# Honey_v2_a.net
KiCad netlist of a schematic drawn in EAGLE
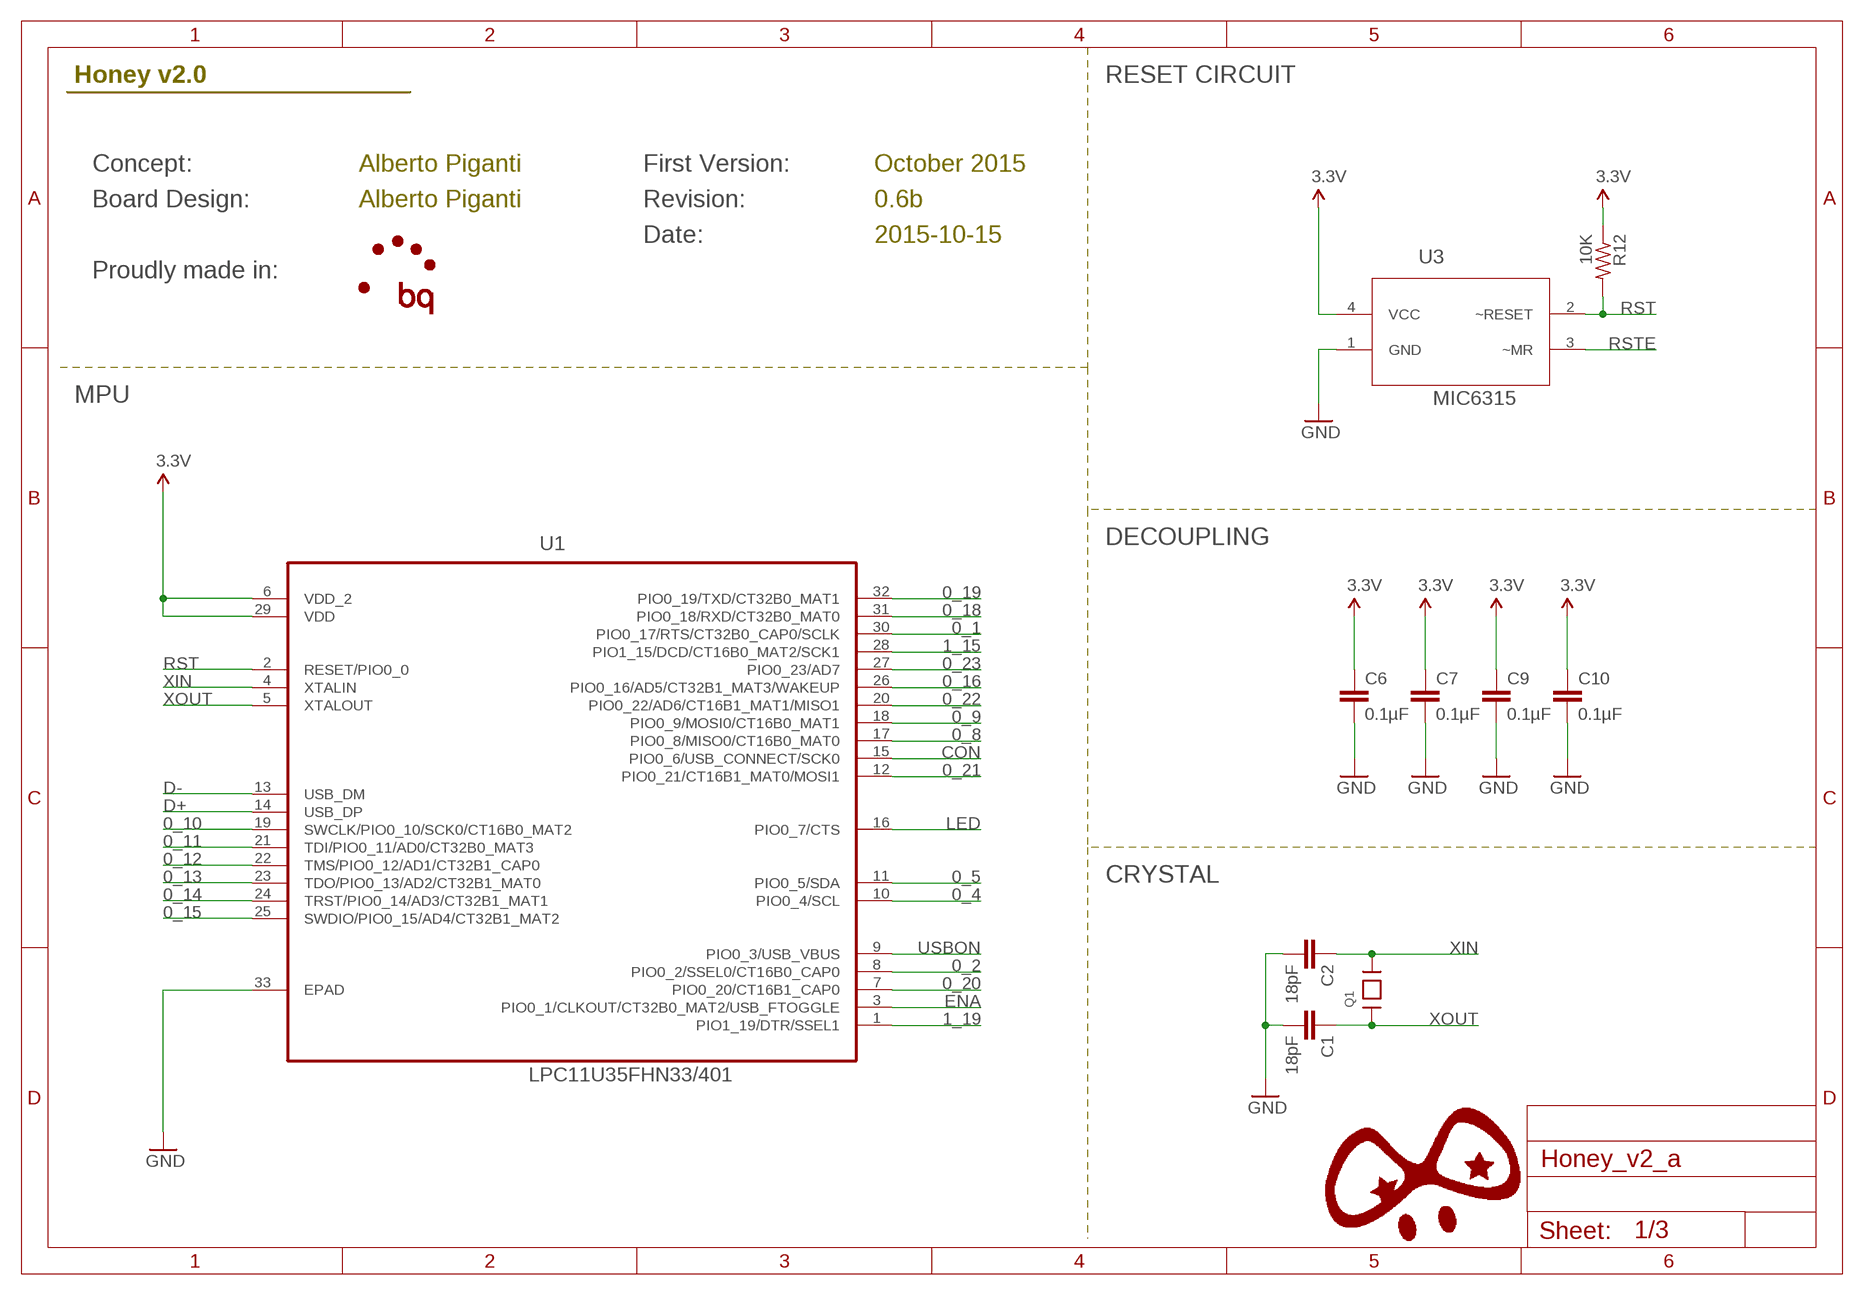
[diagram p0: schematic, sheet 1]
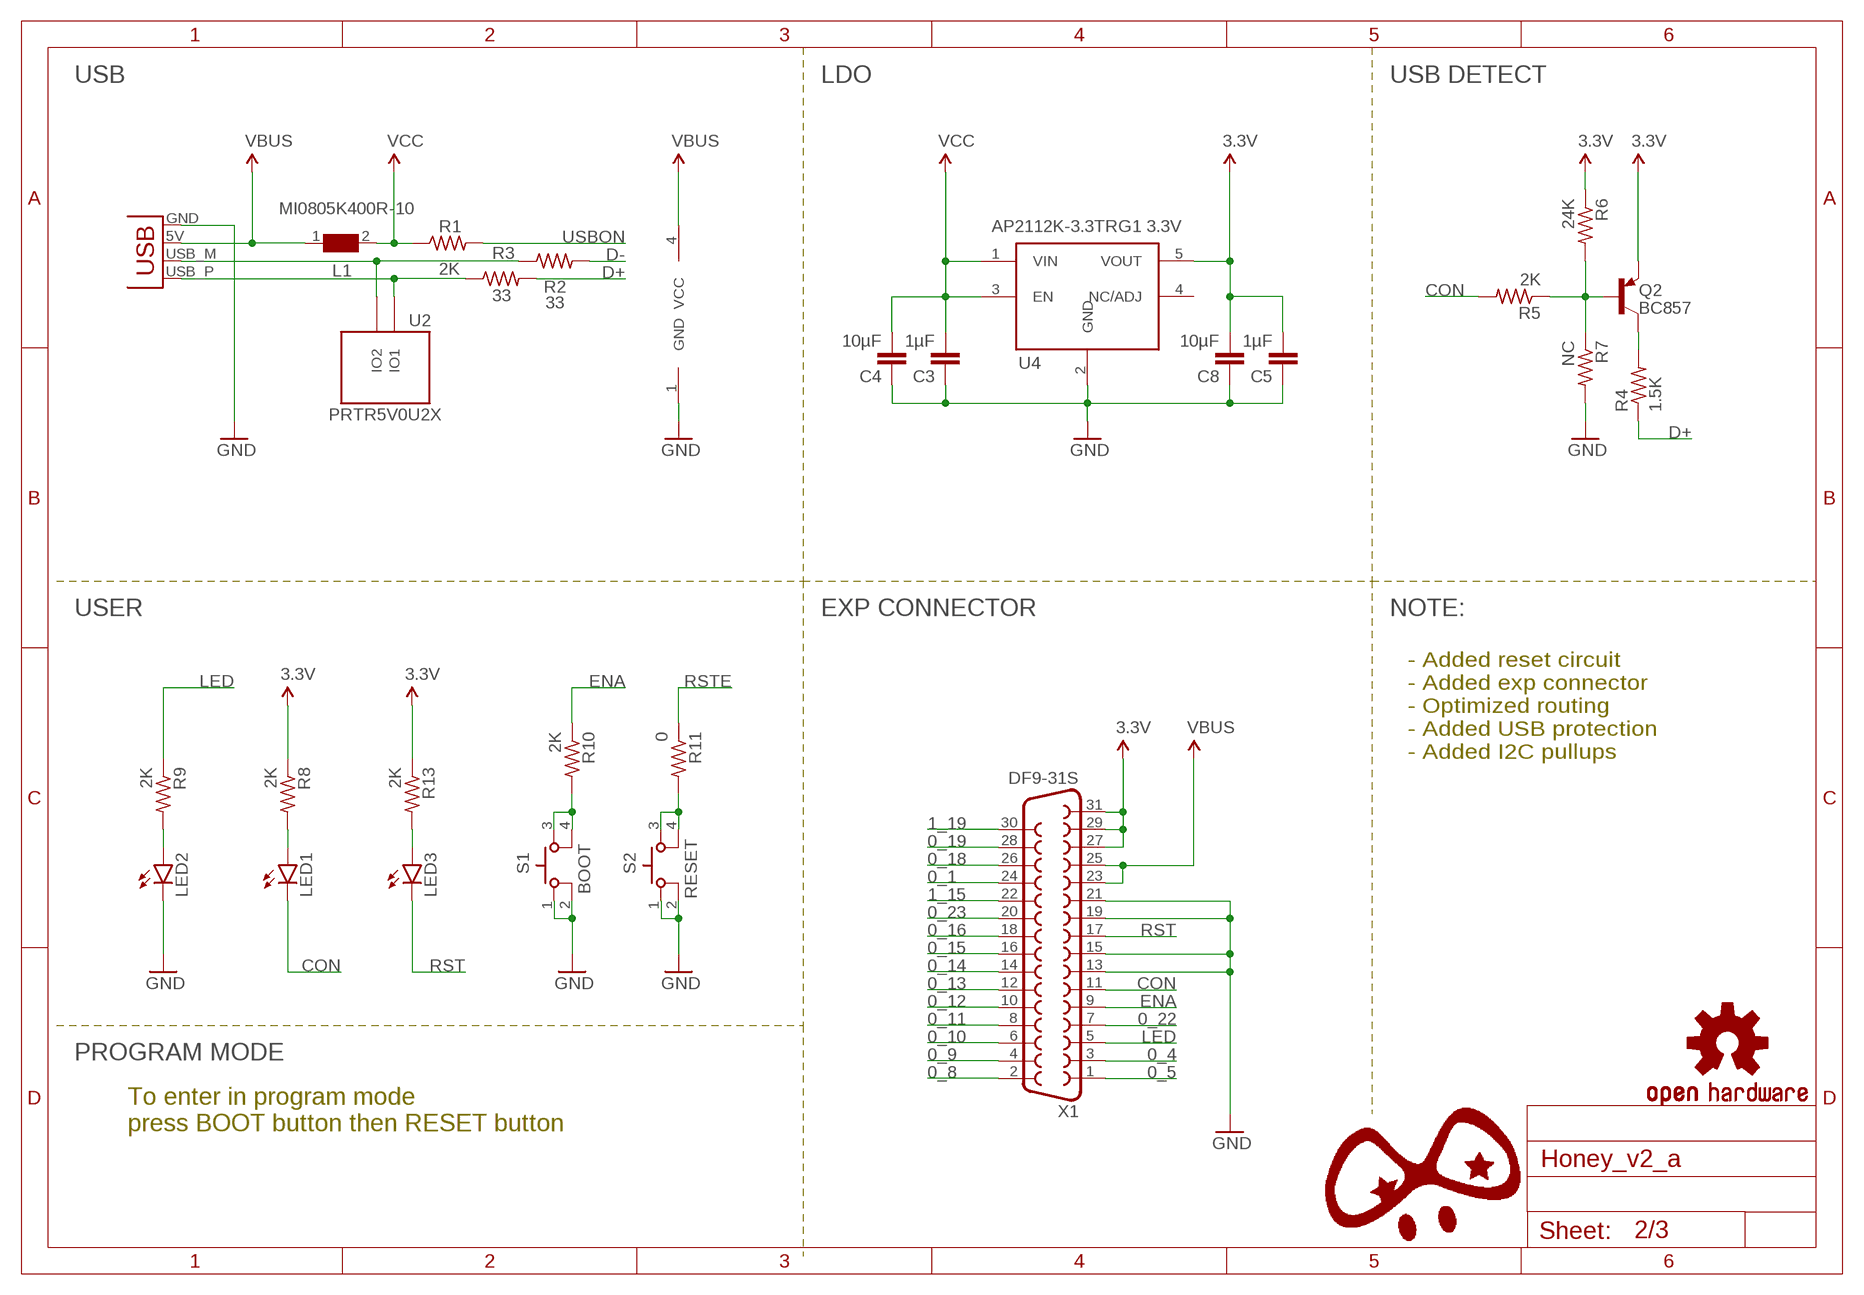
[diagram p1: schematic, sheet 2]
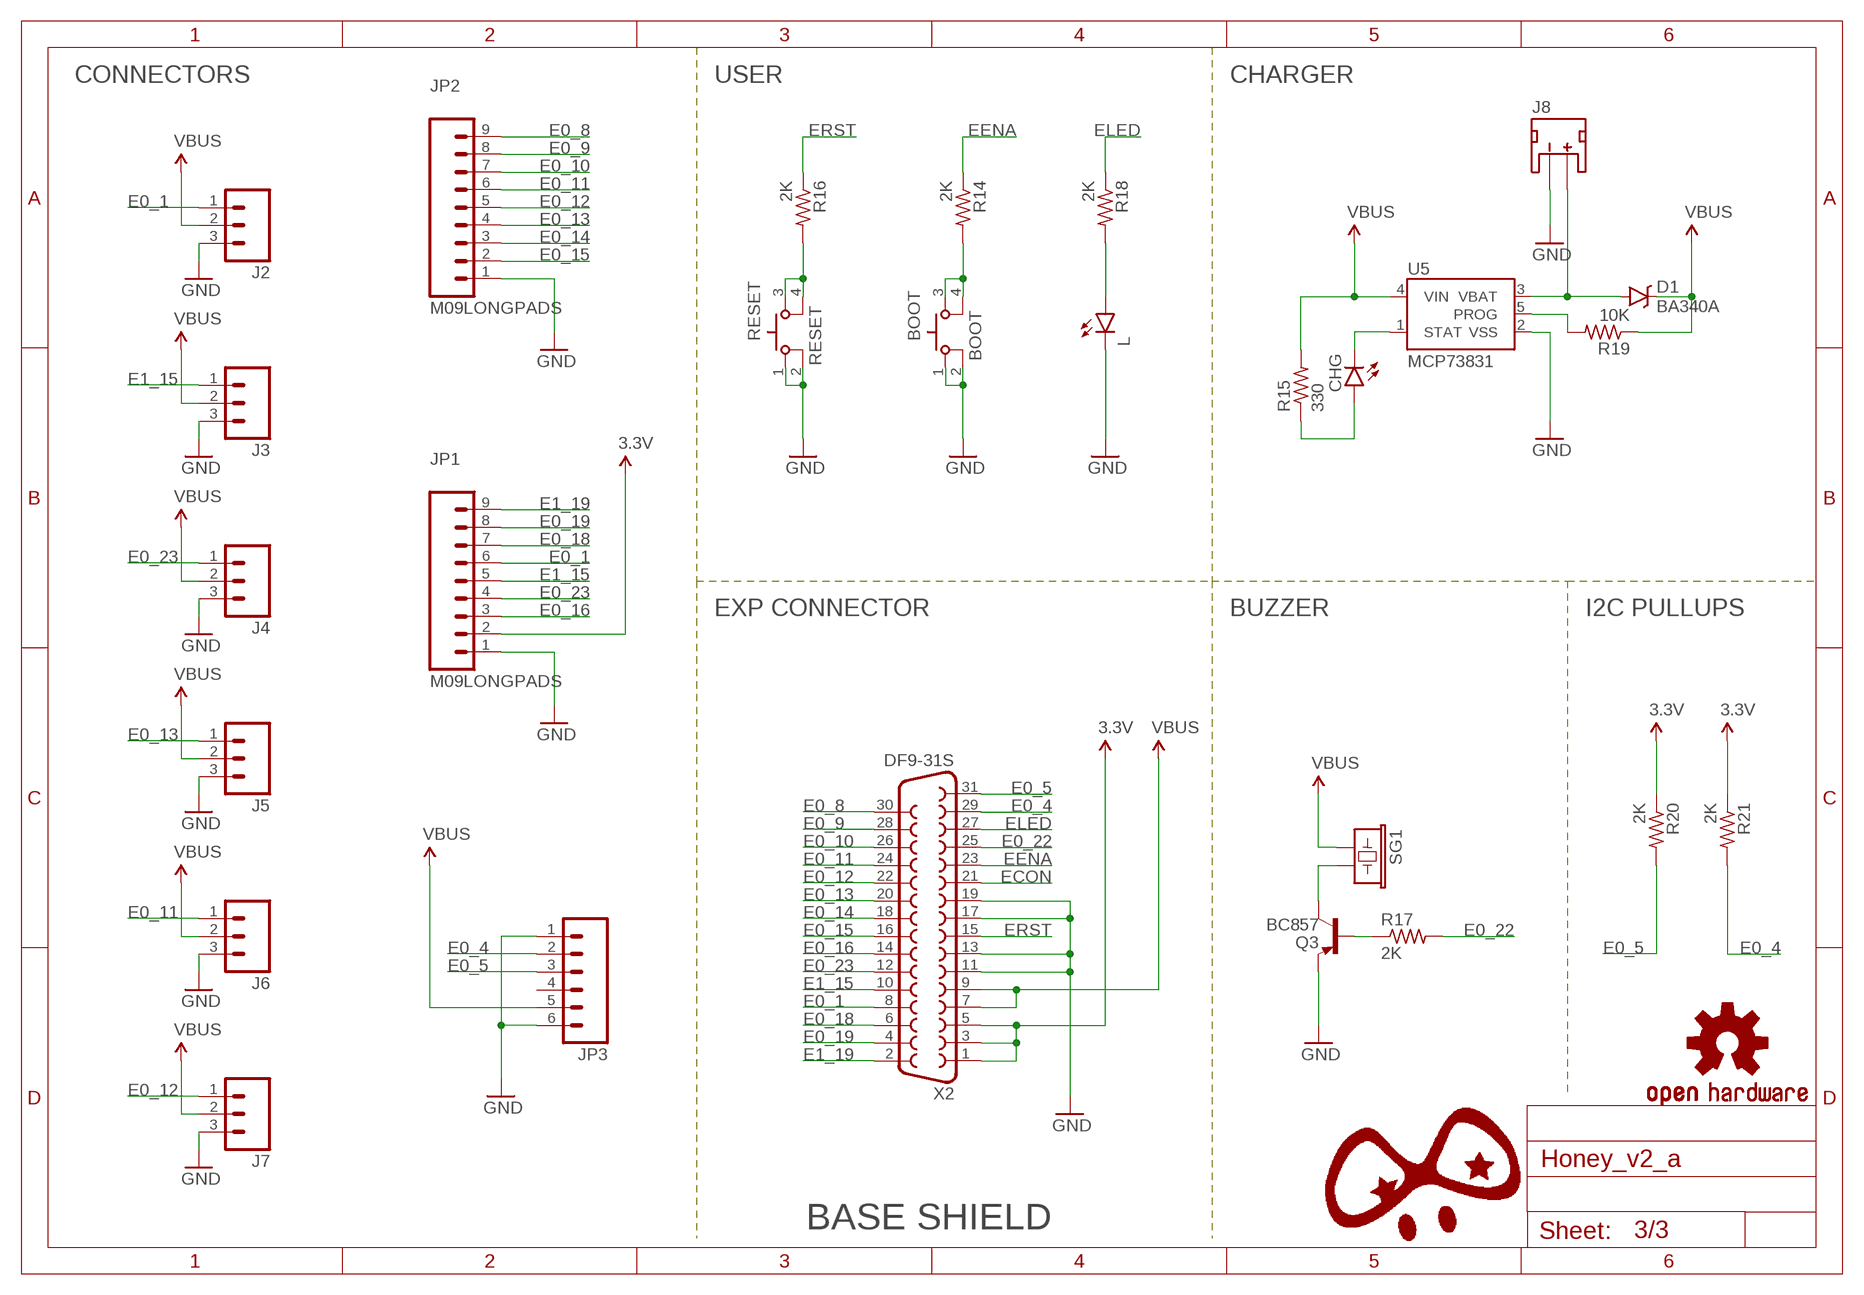
[diagram p2: schematic, sheet 3]

(export (version "E")
  (design (tool "Eeschema 10.0.6"))
  (components
    (comp (ref "C3")
      (value "1µF")
      (footprint "eagle-import:0603-CAP")
      (libsource (lib "eagle-import") (part "CAP0603-CAP"))
    )
    (comp (ref "C4")
      (value "10µF")
      (footprint "eagle-import:0603-CAP")
      (libsource (lib "eagle-import") (part "CAP0603-CAP"))
    )
    (comp (ref "C5")
      (value "1µF")
      (footprint "eagle-import:0603-CAP")
      (libsource (lib "eagle-import") (part "CAP0603-CAP"))
    )
    (comp (ref "C8")
      (value "10µF")
      (footprint "eagle-import:0603-CAP")
      (libsource (lib "eagle-import") (part "CAP0603-CAP"))
    )
    (comp (ref "J1")
      (value "USBPCB")
      (footprint "eagle-import:USB-A-PCB")
      (libsource (lib "eagle-import") (part "USBPCB"))
    )
    (comp (ref "L1")
      (value "MI0805K400R-10")
      (footprint "eagle-import:0805")
      (fields (field (name "MPN") "74279201"))
      (libsource (lib "eagle-import") (part "FERRITE_0805-74279201"))
    )
    (comp (ref "LED1")
      (value "LED0603")
      (footprint "eagle-import:LED-0603")
      (libsource (lib "eagle-import") (part "LED0603"))
    )
    (comp (ref "LED2")
      (value "LED0603")
      (footprint "eagle-import:LED-0603")
      (libsource (lib "eagle-import") (part "LED0603"))
    )
    (comp (ref "LED3")
      (value "LED0603")
      (footprint "eagle-import:LED-0603")
      (libsource (lib "eagle-import") (part "LED0603"))
    )
    (comp (ref "LOGO1")
      (value "OSHW-LOGOS")
      (footprint "eagle-import:OSHW-LOGO-S")
      (libsource (lib "eagle-import") (part "OSHW-LOGOS"))
    )
    (comp (ref "Q2")
      (value "BC857")
      (footprint "eagle-import:SOT23-BEC")
      (libsource (lib "eagle-import") (part "-PNP-SOT23-BECBC857A"))
    )
    (comp (ref "R1")
      (value "2K")
      (footprint "eagle-import:R0402")
      (libsource (lib "eagle-import") (part "R-US_R0402"))
    )
    (comp (ref "R2")
      (value "33")
      (footprint "eagle-import:R0603")
      (libsource (lib "eagle-import") (part "R-US_R0603"))
    )
    (comp (ref "R3")
      (value "33")
      (footprint "eagle-import:R0603")
      (libsource (lib "eagle-import") (part "R-US_R0603"))
    )
    (comp (ref "R4")
      (value "1.5K")
      (footprint "eagle-import:R0402")
      (libsource (lib "eagle-import") (part "R-US_R0402"))
    )
    (comp (ref "R5")
      (value "2K")
      (footprint "eagle-import:R0402")
      (libsource (lib "eagle-import") (part "R-US_R0402"))
    )
    (comp (ref "R6")
      (value "24K")
      (footprint "eagle-import:R0402")
      (libsource (lib "eagle-import") (part "R-US_R0402"))
    )
    (comp (ref "R7")
      (value "NC")
      (footprint "eagle-import:R0402")
      (libsource (lib "eagle-import") (part "R-US_R0402"))
    )
    (comp (ref "R8")
      (value "2K")
      (footprint "eagle-import:R0402")
      (libsource (lib "eagle-import") (part "R-US_R0402"))
    )
    (comp (ref "R9")
      (value "2K")
      (footprint "eagle-import:R0402")
      (libsource (lib "eagle-import") (part "R-US_R0402"))
    )
    (comp (ref "R10")
      (value "2K")
      (footprint "eagle-import:R0402")
      (libsource (lib "eagle-import") (part "R-US_R0402"))
    )
    (comp (ref "R11")
      (value "0")
      (footprint "eagle-import:R0402")
      (libsource (lib "eagle-import") (part "R-US_R0402"))
    )
    (comp (ref "R13")
      (value "2K")
      (footprint "eagle-import:R0402")
      (libsource (lib "eagle-import") (part "R-US_R0402"))
    )
    (comp (ref "S1")
      (value "BOOT")
      (footprint "eagle-import:MINI_PUSHBUTTON")
      (libsource (lib "eagle-import") (part "MINI_PUSHBUTTON"))
    )
    (comp (ref "S2")
      (value "RESET")
      (footprint "eagle-import:MINI_PUSHBUTTON")
      (libsource (lib "eagle-import") (part "MINI_PUSHBUTTON"))
    )
    (comp (ref "U2")
      (value "PRTR5V0U2X")
      (footprint "eagle-import:SOT-143B")
      (fields
        (field (name "MANUFACTURER") "NXP Semiconductors")
        (field (name "PART_NUMBER") "PRTR5V0U2X,215")
      )
      (libsource (lib "eagle-import") (part "PRTR5V0U2X?"))
    )
    (comp (ref "U4")
      (value "AP2112K-3.3TRG1 3.3V")
      (footprint "eagle-import:SOT23-5")
      (libsource (lib "eagle-import") (part "5PIN_REG"))
    )
    (comp (ref "X1")
      (value "DF9-31S")
      (footprint "eagle-import:DF9-31S")
      (fields (field (name "MPN") "DF9-31S-1V(32)"))
      (libsource (lib "eagle-import") (part "DF9-31S"))
    )
    (comp (ref "BOOT")
      (value "BOOT")
      (footprint "eagle-import:MINI_PUSHBUTTON")
      (libsource (lib "eagle-import") (part "MINI_PUSHBUTTON"))
    )
    (comp (ref "CHG")
      (value "LED0603")
      (footprint "eagle-import:LED-0603")
      (libsource (lib "eagle-import") (part "LED0603"))
    )
    (comp (ref "D1")
      (value "BA340A")
      (footprint "eagle-import:SMA-DIODE")
      (libsource (lib "eagle-import") (part "B340A"))
    )
    (comp (ref "J2")
      (value "M03LOCK_NO_SILK")
      (footprint "eagle-import:1X03_LOCK_NO_SILK")
      (libsource (lib "eagle-import") (part "M03LOCK_NO_SILK"))
    )
    (comp (ref "J3")
      (value "M03LOCK_NO_SILK")
      (footprint "eagle-import:1X03_LOCK_NO_SILK")
      (libsource (lib "eagle-import") (part "M03LOCK_NO_SILK"))
    )
    (comp (ref "J4")
      (value "M03LOCK_NO_SILK")
      (footprint "eagle-import:1X03_LOCK_NO_SILK")
      (libsource (lib "eagle-import") (part "M03LOCK_NO_SILK"))
    )
    (comp (ref "J5")
      (value "M03LOCK_NO_SILK")
      (footprint "eagle-import:1X03_LOCK_NO_SILK")
      (libsource (lib "eagle-import") (part "M03LOCK_NO_SILK"))
    )
    (comp (ref "J6")
      (value "M03LOCK_NO_SILK")
      (footprint "eagle-import:1X03_LOCK_NO_SILK")
      (libsource (lib "eagle-import") (part "M03LOCK_NO_SILK"))
    )
    (comp (ref "J7")
      (value "M03LOCK_NO_SILK")
      (footprint "eagle-import:1X03_LOCK_NO_SILK")
      (libsource (lib "eagle-import") (part "M03LOCK_NO_SILK"))
    )
    (comp (ref "J8")
      (value "JST_2MM_MALE")
      (footprint "eagle-import:JST-2-SMD")
      (libsource (lib "eagle-import") (part "JST_2MM_MALE"))
    )
    (comp (ref "JP1")
      (value "M09LONGPADS")
      (footprint "eagle-import:1X09_LONGPADS")
      (libsource (lib "eagle-import") (part "M09LONGPADS"))
    )
    (comp (ref "JP2")
      (value "M09LONGPADS")
      (footprint "eagle-import:1X09_LONGPADS")
      (libsource (lib "eagle-import") (part "M09LONGPADS"))
    )
    (comp (ref "JP3")
      (value "M06LONGPADS")
      (footprint "eagle-import:1X06_LONGPADS")
      (libsource (lib "eagle-import") (part "M06LONGPADS"))
    )
    (comp (ref "L")
      (value "LED0603")
      (footprint "eagle-import:LED-0603")
      (libsource (lib "eagle-import") (part "LED0603"))
    )
    (comp (ref "LOGO4")
      (value "OSHW-LOGOS")
      (footprint "eagle-import:OSHW-LOGO-S")
      (libsource (lib "eagle-import") (part "OSHW-LOGOS"))
    )
    (comp (ref "Q3")
      (value "BC857")
      (footprint "eagle-import:SOT23-BEC")
      (libsource (lib "eagle-import") (part "-PNP-SOT23-BECBC857A"))
    )
    (comp (ref "R14")
      (value "2K")
      (footprint "eagle-import:R0402")
      (libsource (lib "eagle-import") (part "R-US_R0402"))
    )
    (comp (ref "R15")
      (value "330")
      (footprint "eagle-import:R0402")
      (libsource (lib "eagle-import") (part "R-US_R0402"))
    )
    (comp (ref "R16")
      (value "2K")
      (footprint "eagle-import:R0402")
      (libsource (lib "eagle-import") (part "R-US_R0402"))
    )
    (comp (ref "R17")
      (value "2K")
      (footprint "eagle-import:R0402")
      (libsource (lib "eagle-import") (part "R-US_R0402"))
    )
    (comp (ref "R18")
      (value "2K")
      (footprint "eagle-import:R0402")
      (libsource (lib "eagle-import") (part "R-US_R0402"))
    )
    (comp (ref "R19")
      (value "10K")
      (footprint "eagle-import:R0402")
      (libsource (lib "eagle-import") (part "R-US_R0402"))
    )
    (comp (ref "R20")
      (value "2K")
      (footprint "eagle-import:R0402")
      (libsource (lib "eagle-import") (part "R-US_R0402"))
    )
    (comp (ref "R21")
      (value "2K")
      (footprint "eagle-import:R0402")
      (libsource (lib "eagle-import") (part "R-US_R0402"))
    )
    (comp (ref "RESET")
      (value "RESET")
      (footprint "eagle-import:MINI_PUSHBUTTON")
      (libsource (lib "eagle-import") (part "MINI_PUSHBUTTON"))
    )
    (comp (ref "SG1")
      (value "BUZZERSMD2")
      (footprint "eagle-import:BUZZER-CCV")
      (libsource (lib "eagle-import") (part "BUZZERSMD2"))
    )
    (comp (ref "U5")
      (value "MCP73831")
      (footprint "eagle-import:SOT23-5")
      (libsource (lib "eagle-import") (part "MCP73831"))
    )
    (comp (ref "X2")
      (value "DF9-31S")
      (footprint "eagle-import:DF9-31S")
      (fields (field (name "MPN") "DF9-31S-1V(32)"))
      (libsource (lib "eagle-import") (part "DF9-31S"))
    )
    (comp (ref "C1")
      (value "18pF")
      (footprint "eagle-import:C0402")
      (libsource (lib "eagle-import") (part "C-EUC0402"))
    )
    (comp (ref "C2")
      (value "18pF")
      (footprint "eagle-import:C0402")
      (libsource (lib "eagle-import") (part "C-EUC0402"))
    )
    (comp (ref "C6")
      (value "0.1µF")
      (footprint "eagle-import:C0402")
      (libsource (lib "eagle-import") (part "C-EUC0402"))
    )
    (comp (ref "C7")
      (value "0.1µF")
      (footprint "eagle-import:C0402")
      (libsource (lib "eagle-import") (part "C-EUC0402"))
    )
    (comp (ref "C9")
      (value "0.1µF")
      (footprint "eagle-import:C0402")
      (libsource (lib "eagle-import") (part "C-EUC0402"))
    )
    (comp (ref "C10")
      (value "0.1µF")
      (footprint "eagle-import:C0402")
      (libsource (lib "eagle-import") (part "C-EUC0402"))
    )
    (comp (ref "Q1")
      (value "12MHz 4 pad crystal 3.2x2.5")
      (footprint "eagle-import:CRYSTAL_3.2X2.5")
      (libsource (lib "eagle-import") (part "CRYSTAL3.2X2.5"))
    )
    (comp (ref "R12")
      (value "10K")
      (footprint "eagle-import:R0402")
      (libsource (lib "eagle-import") (part "R-US_R0402"))
    )
    (comp (ref "U1")
      (value "LPC11U35FHN33/401")
      (footprint "eagle-import:QFN65P700X700X100-33N")
      (libsource (lib "eagle-import") (part "LPC11U35FHN33/401"))
    )
    (comp (ref "U3")
      (value "MIC6315")
      (footprint "eagle-import:SOT-143B")
      (libsource (lib "eagle-import") (part "MIC6315"))
    )
  )
  (nets
    (net (code "1") (name "0_1") (class "Default")
      (node (ref "U1") (pin "30") (pinfunction "PIO0_17/RTS/CT32B0_CAP0/SCLK_30") (pintype "bidirectional"))
      (node (ref "X1") (pin "24") (pinfunction "24_24") (pintype "passive"))
    )
    (net (code "2") (name "0_2") (class "Default")
      (node (ref "U1") (pin "8") (pinfunction "PIO0_2/SSEL0/CT16B0_CAP0_8") (pintype "bidirectional"))
    )
    (net (code "3") (name "0_4") (class "Default")
      (node (ref "U1") (pin "10") (pinfunction "PIO0_4/SCL_10") (pintype "bidirectional"))
      (node (ref "X1") (pin "3") (pinfunction "3_3") (pintype "passive"))
    )
    (net (code "4") (name "0_5") (class "Default")
      (node (ref "U1") (pin "11") (pinfunction "PIO0_5/SDA_11") (pintype "bidirectional"))
      (node (ref "X1") (pin "1") (pinfunction "1_1") (pintype "passive"))
    )
    (net (code "5") (name "0_8") (class "Default")
      (node (ref "U1") (pin "17") (pinfunction "PIO0_8/MISO0/CT16B0_MAT0_17") (pintype "bidirectional"))
      (node (ref "X1") (pin "2") (pinfunction "2_2") (pintype "passive"))
    )
    (net (code "6") (name "0_9") (class "Default")
      (node (ref "U1") (pin "18") (pinfunction "PIO0_9/MOSI0/CT16B0_MAT1_18") (pintype "bidirectional"))
      (node (ref "X1") (pin "4") (pinfunction "4_4") (pintype "passive"))
    )
    (net (code "7") (name "0_10") (class "Default")
      (node (ref "U1") (pin "19") (pinfunction "SWCLK/PIO0_10/SCK0/CT16B0_MAT2_19") (pintype "input"))
      (node (ref "X1") (pin "6") (pinfunction "6_6") (pintype "passive"))
    )
    (net (code "8") (name "0_11") (class "Default")
      (node (ref "U1") (pin "21") (pinfunction "TDI/PIO0_11/AD0/CT32B0_MAT3_21") (pintype "input"))
      (node (ref "X1") (pin "8") (pinfunction "8_8") (pintype "passive"))
    )
    (net (code "9") (name "0_12") (class "Default")
      (node (ref "U1") (pin "22") (pinfunction "TMS/PIO0_12/AD1/CT32B1_CAP0_22") (pintype "input"))
      (node (ref "X1") (pin "10") (pinfunction "10_10") (pintype "passive"))
    )
    (net (code "10") (name "0_13") (class "Default")
      (node (ref "U1") (pin "23") (pinfunction "TDO/PIO0_13/AD2/CT32B1_MAT0_23") (pintype "output"))
      (node (ref "X1") (pin "12") (pinfunction "12_12") (pintype "passive"))
    )
    (net (code "11") (name "0_14") (class "Default")
      (node (ref "U1") (pin "24") (pinfunction "TRST/PIO0_14/AD3/CT32B1_MAT1_24") (pintype "input"))
      (node (ref "X1") (pin "14") (pinfunction "14_14") (pintype "passive"))
    )
    (net (code "12") (name "0_15") (class "Default")
      (node (ref "U1") (pin "25") (pinfunction "SWDIO/PIO0_15/AD4/CT32B1_MAT2_25") (pintype "output"))
      (node (ref "X1") (pin "16") (pinfunction "16_16") (pintype "passive"))
    )
    (net (code "13") (name "0_16") (class "Default")
      (node (ref "U1") (pin "26") (pinfunction "PIO0_16/AD5/CT32B1_MAT3/WAKEUP_26") (pintype "bidirectional"))
      (node (ref "X1") (pin "18") (pinfunction "18_18") (pintype "passive"))
    )
    (net (code "14") (name "0_18") (class "Default")
      (node (ref "U1") (pin "31") (pinfunction "PIO0_18/RXD/CT32B0_MAT0_31") (pintype "bidirectional"))
      (node (ref "X1") (pin "26") (pinfunction "26_26") (pintype "passive"))
    )
    (net (code "15") (name "0_19") (class "Default")
      (node (ref "U1") (pin "32") (pinfunction "PIO0_19/TXD/CT32B0_MAT1_32") (pintype "bidirectional"))
      (node (ref "X1") (pin "28") (pinfunction "28_28") (pintype "passive"))
    )
    (net (code "16") (name "0_20") (class "Default")
      (node (ref "U1") (pin "7") (pinfunction "PIO0_20/CT16B1_CAP0_7") (pintype "bidirectional"))
    )
    (net (code "17") (name "0_21") (class "Default")
      (node (ref "U1") (pin "12") (pinfunction "PIO0_21/CT16B1_MAT0/MOSI1_12") (pintype "bidirectional"))
    )
    (net (code "18") (name "0_22") (class "Default")
      (node (ref "U1") (pin "20") (pinfunction "PIO0_22/AD6/CT16B1_MAT1/MISO1_20") (pintype "bidirectional"))
      (node (ref "X1") (pin "7") (pinfunction "7_7") (pintype "passive"))
    )
    (net (code "19") (name "0_23") (class "Default")
      (node (ref "U1") (pin "27") (pinfunction "PIO0_23/AD7_27") (pintype "bidirectional"))
      (node (ref "X1") (pin "20") (pinfunction "20_20") (pintype "passive"))
    )
    (net (code "20") (name "1_15") (class "Default")
      (node (ref "U1") (pin "28") (pinfunction "PIO1_15/DCD/CT16B0_MAT2/SCK1_28") (pintype "bidirectional"))
      (node (ref "X1") (pin "22") (pinfunction "22_22") (pintype "passive"))
    )
    (net (code "21") (name "1_19") (class "Default")
      (node (ref "U1") (pin "1") (pinfunction "PIO1_19/DTR/SSEL1_1") (pintype "bidirectional"))
      (node (ref "X1") (pin "30") (pinfunction "30_30") (pintype "passive"))
    )
    (net (code "22") (name "3.3V") (class "Default")
      (node (ref "C10") (pin "1") (pinfunction "1_1") (pintype "passive"))
      (node (ref "C5") (pin "2") (pinfunction "2_2") (pintype "passive"))
      (node (ref "C6") (pin "1") (pinfunction "1_1") (pintype "passive"))
      (node (ref "C7") (pin "1") (pinfunction "1_1") (pintype "passive"))
      (node (ref "C8") (pin "2") (pinfunction "2_2") (pintype "passive"))
      (node (ref "C9") (pin "1") (pinfunction "1_1") (pintype "passive"))
      (node (ref "JP1") (pin "2") (pinfunction "2_2") (pintype "passive"))
      (node (ref "Q2") (pin "E") (pinfunction "E_E") (pintype "passive"))
      (node (ref "R12") (pin "1") (pinfunction "1_1") (pintype "passive"))
      (node (ref "R13") (pin "1") (pinfunction "1_1") (pintype "passive"))
      (node (ref "R20") (pin "1") (pinfunction "1_1") (pintype "passive"))
      (node (ref "R21") (pin "1") (pinfunction "1_1") (pintype "passive"))
      (node (ref "R6") (pin "1") (pinfunction "1_1") (pintype "passive"))
      (node (ref "R8") (pin "1") (pinfunction "1_1") (pintype "passive"))
      (node (ref "U1") (pin "29") (pinfunction "VDD_29") (pintype "power_in"))
      (node (ref "U1") (pin "6") (pinfunction "VDD_2_6") (pintype "power_in"))
      (node (ref "U3") (pin "4") (pinfunction "VCC_4") (pintype "power_in"))
      (node (ref "U4") (pin "5") (pinfunction "VOUT_5") (pintype "bidirectional"))
      (node (ref "X1") (pin "27") (pinfunction "27_27") (pintype "passive"))
      (node (ref "X1") (pin "29") (pinfunction "29_29") (pintype "passive"))
      (node (ref "X1") (pin "31") (pinfunction "31_31") (pintype "passive"))
      (node (ref "X2") (pin "1") (pinfunction "1_1") (pintype "passive"))
      (node (ref "X2") (pin "3") (pinfunction "3_3") (pintype "passive"))
      (node (ref "X2") (pin "5") (pinfunction "5_5") (pintype "passive"))
    )
    (net (code "23") (name "CON") (class "Default")
      (node (ref "LED1") (pin "C") (pinfunction "C_C") (pintype "passive"))
      (node (ref "R5") (pin "2") (pinfunction "2_2") (pintype "passive"))
      (node (ref "U1") (pin "15") (pinfunction "PIO0_6/USB_CONNECT/SCK0_15") (pintype "bidirectional"))
      (node (ref "X1") (pin "11") (pinfunction "11_11") (pintype "passive"))
    )
    (net (code "24") (name "D+") (class "Default")
      (node (ref "R3") (pin "2") (pinfunction "2_2") (pintype "passive"))
      (node (ref "R4") (pin "1") (pinfunction "1_1") (pintype "passive"))
      (node (ref "U1") (pin "14") (pinfunction "USB_DP_14") (pintype "passive"))
    )
    (net (code "25") (name "D-") (class "Default")
      (node (ref "R2") (pin "2") (pinfunction "2_2") (pintype "passive"))
      (node (ref "U1") (pin "13") (pinfunction "USB_DM_13") (pintype "passive"))
    )
    (net (code "26") (name "E0_1") (class "Default")
      (node (ref "J2") (pin "1") (pinfunction "1_1") (pintype "passive"))
      (node (ref "JP1") (pin "6") (pinfunction "6_6") (pintype "passive"))
      (node (ref "X2") (pin "8") (pinfunction "8_8") (pintype "passive"))
    )
    (net (code "27") (name "E0_4") (class "Default")
      (node (ref "JP3") (pin "2") (pinfunction "2_2") (pintype "passive"))
      (node (ref "R21") (pin "2") (pinfunction "2_2") (pintype "passive"))
      (node (ref "X2") (pin "29") (pinfunction "29_29") (pintype "passive"))
    )
    (net (code "28") (name "E0_5") (class "Default")
      (node (ref "JP3") (pin "3") (pinfunction "3_3") (pintype "passive"))
      (node (ref "R20") (pin "2") (pinfunction "2_2") (pintype "passive"))
      (node (ref "X2") (pin "31") (pinfunction "31_31") (pintype "passive"))
    )
    (net (code "29") (name "E0_8") (class "Default")
      (node (ref "JP2") (pin "9") (pinfunction "9_9") (pintype "passive"))
      (node (ref "X2") (pin "30") (pinfunction "30_30") (pintype "passive"))
    )
    (net (code "30") (name "E0_9") (class "Default")
      (node (ref "JP2") (pin "8") (pinfunction "8_8") (pintype "passive"))
      (node (ref "X2") (pin "28") (pinfunction "28_28") (pintype "passive"))
    )
    (net (code "31") (name "E0_10") (class "Default")
      (node (ref "JP2") (pin "7") (pinfunction "7_7") (pintype "passive"))
      (node (ref "X2") (pin "26") (pinfunction "26_26") (pintype "passive"))
    )
    (net (code "32") (name "E0_11") (class "Default")
      (node (ref "J6") (pin "1") (pinfunction "1_1") (pintype "passive"))
      (node (ref "JP2") (pin "6") (pinfunction "6_6") (pintype "passive"))
      (node (ref "X2") (pin "24") (pinfunction "24_24") (pintype "passive"))
    )
    (net (code "33") (name "E0_12") (class "Default")
      (node (ref "J7") (pin "1") (pinfunction "1_1") (pintype "passive"))
      (node (ref "JP2") (pin "5") (pinfunction "5_5") (pintype "passive"))
      (node (ref "X2") (pin "22") (pinfunction "22_22") (pintype "passive"))
    )
    (net (code "34") (name "E0_13") (class "Default")
      (node (ref "J5") (pin "1") (pinfunction "1_1") (pintype "passive"))
      (node (ref "JP2") (pin "4") (pinfunction "4_4") (pintype "passive"))
      (node (ref "X2") (pin "20") (pinfunction "20_20") (pintype "passive"))
    )
    (net (code "35") (name "E0_14") (class "Default")
      (node (ref "JP2") (pin "3") (pinfunction "3_3") (pintype "passive"))
      (node (ref "X2") (pin "18") (pinfunction "18_18") (pintype "passive"))
    )
    (net (code "36") (name "E0_15") (class "Default")
      (node (ref "JP2") (pin "2") (pinfunction "2_2") (pintype "passive"))
      (node (ref "X2") (pin "16") (pinfunction "16_16") (pintype "passive"))
    )
    (net (code "37") (name "E0_16") (class "Default")
      (node (ref "JP1") (pin "3") (pinfunction "3_3") (pintype "passive"))
      (node (ref "X2") (pin "14") (pinfunction "14_14") (pintype "passive"))
    )
    (net (code "38") (name "E0_18") (class "Default")
      (node (ref "JP1") (pin "7") (pinfunction "7_7") (pintype "passive"))
      (node (ref "X2") (pin "6") (pinfunction "6_6") (pintype "passive"))
    )
    (net (code "39") (name "E0_19") (class "Default")
      (node (ref "JP1") (pin "8") (pinfunction "8_8") (pintype "passive"))
      (node (ref "X2") (pin "4") (pinfunction "4_4") (pintype "passive"))
    )
    (net (code "40") (name "E0_22") (class "Default")
      (node (ref "R17") (pin "2") (pinfunction "2_2") (pintype "passive"))
      (node (ref "X2") (pin "25") (pinfunction "25_25") (pintype "passive"))
    )
    (net (code "41") (name "E0_23") (class "Default")
      (node (ref "J4") (pin "1") (pinfunction "1_1") (pintype "passive"))
      (node (ref "JP1") (pin "4") (pinfunction "4_4") (pintype "passive"))
      (node (ref "X2") (pin "12") (pinfunction "12_12") (pintype "passive"))
    )
    (net (code "42") (name "E1_15") (class "Default")
      (node (ref "J3") (pin "1") (pinfunction "1_1") (pintype "passive"))
      (node (ref "JP1") (pin "5") (pinfunction "5_5") (pintype "passive"))
      (node (ref "X2") (pin "10") (pinfunction "10_10") (pintype "passive"))
    )
    (net (code "43") (name "E1_19") (class "Default")
      (node (ref "JP1") (pin "9") (pinfunction "9_9") (pintype "passive"))
      (node (ref "X2") (pin "2") (pinfunction "2_2") (pintype "passive"))
    )
    (net (code "44") (name "ECON") (class "Default")
      (node (ref "X2") (pin "21") (pinfunction "21_21") (pintype "passive"))
    )
    (net (code "45") (name "EENA") (class "Default")
      (node (ref "R14") (pin "1") (pinfunction "1_1") (pintype "passive"))
      (node (ref "X2") (pin "23") (pinfunction "23_23") (pintype "passive"))
    )
    (net (code "46") (name "ELED") (class "Default")
      (node (ref "R18") (pin "1") (pinfunction "1_1") (pintype "passive"))
      (node (ref "X2") (pin "27") (pinfunction "27_27") (pintype "passive"))
    )
    (net (code "47") (name "ENA") (class "Default")
      (node (ref "R10") (pin "1") (pinfunction "1_1") (pintype "passive"))
      (node (ref "U1") (pin "3") (pinfunction "PIO0_1/CLKOUT/CT32B0_MAT2/USB_FTOGGLE_3") (pintype "bidirectional"))
      (node (ref "X1") (pin "9") (pinfunction "9_9") (pintype "passive"))
    )
    (net (code "48") (name "ERST") (class "Default")
      (node (ref "R16") (pin "1") (pinfunction "1_1") (pintype "passive"))
      (node (ref "X2") (pin "15") (pinfunction "15_15") (pintype "passive"))
    )
    (net (code "49") (name "GND") (class "Default")
      (node (ref "BOOT") (pin "1") (pinfunction "1_1") (pintype "bidirectional"))
      (node (ref "BOOT") (pin "2") (pinfunction "2_2") (pintype "bidirectional"))
      (node (ref "C1") (pin "2") (pinfunction "2_2") (pintype "passive"))
      (node (ref "C10") (pin "2") (pinfunction "2_2") (pintype "passive"))
      (node (ref "C2") (pin "2") (pinfunction "2_2") (pintype "passive"))
      (node (ref "C3") (pin "1") (pinfunction "1_1") (pintype "passive"))
      (node (ref "C4") (pin "1") (pinfunction "1_1") (pintype "passive"))
      (node (ref "C5") (pin "1") (pinfunction "1_1") (pintype "passive"))
      (node (ref "C6") (pin "2") (pinfunction "2_2") (pintype "passive"))
      (node (ref "C7") (pin "2") (pinfunction "2_2") (pintype "passive"))
      (node (ref "C8") (pin "1") (pinfunction "1_1") (pintype "passive"))
      (node (ref "C9") (pin "2") (pinfunction "2_2") (pintype "passive"))
      (node (ref "J1") (pin "GND") (pinfunction "GND_GND") (pintype "bidirectional"))
      (node (ref "J2") (pin "3") (pinfunction "3_3") (pintype "passive"))
      (node (ref "J3") (pin "3") (pinfunction "3_3") (pintype "passive"))
      (node (ref "J4") (pin "3") (pinfunction "3_3") (pintype "passive"))
      (node (ref "J5") (pin "3") (pinfunction "3_3") (pintype "passive"))
      (node (ref "J6") (pin "3") (pinfunction "3_3") (pintype "passive"))
      (node (ref "J7") (pin "3") (pinfunction "3_3") (pintype "passive"))
      (node (ref "J8") (pin "1") (pinfunction "-_1") (pintype "bidirectional"))
      (node (ref "JP1") (pin "1") (pinfunction "1_1") (pintype "passive"))
      (node (ref "JP2") (pin "1") (pinfunction "1_1") (pintype "passive"))
      (node (ref "JP3") (pin "1") (pinfunction "1_1") (pintype "passive"))
      (node (ref "JP3") (pin "6") (pinfunction "6_6") (pintype "passive"))
      (node (ref "L") (pin "C") (pinfunction "C_C") (pintype "passive"))
      (node (ref "LED2") (pin "C") (pinfunction "C_C") (pintype "passive"))
      (node (ref "Q3") (pin "E") (pinfunction "E_E") (pintype "passive"))
      (node (ref "R7") (pin "2") (pinfunction "2_2") (pintype "passive"))
      (node (ref "RESET") (pin "1") (pinfunction "1_1") (pintype "bidirectional"))
      (node (ref "RESET") (pin "2") (pinfunction "2_2") (pintype "bidirectional"))
      (node (ref "S1") (pin "1") (pinfunction "1_1") (pintype "bidirectional"))
      (node (ref "S1") (pin "2") (pinfunction "2_2") (pintype "bidirectional"))
      (node (ref "S2") (pin "1") (pinfunction "1_1") (pintype "bidirectional"))
      (node (ref "S2") (pin "2") (pinfunction "2_2") (pintype "bidirectional"))
      (node (ref "U1") (pin "33") (pinfunction "EPAD_33") (pintype "passive"))
      (node (ref "U2") (pin "1") (pinfunction "GND_1") (pintype "bidirectional"))
      (node (ref "U3") (pin "1") (pinfunction "GND_1") (pintype "passive"))
      (node (ref "U4") (pin "2") (pinfunction "GND_2") (pintype "bidirectional"))
      (node (ref "U5") (pin "2") (pinfunction "VSS_2") (pintype "power_in"))
      (node (ref "X1") (pin "13") (pinfunction "13_13") (pintype "passive"))
      (node (ref "X1") (pin "15") (pinfunction "15_15") (pintype "passive"))
      (node (ref "X1") (pin "19") (pinfunction "19_19") (pintype "passive"))
      (node (ref "X1") (pin "21") (pinfunction "21_21") (pintype "passive"))
      (node (ref "X2") (pin "11") (pinfunction "11_11") (pintype "passive"))
      (node (ref "X2") (pin "13") (pinfunction "13_13") (pintype "passive"))
      (node (ref "X2") (pin "17") (pinfunction "17_17") (pintype "passive"))
      (node (ref "X2") (pin "19") (pinfunction "19_19") (pintype "passive"))
    )
    (net (code "50") (name "LED") (class "Default")
      (node (ref "R9") (pin "1") (pinfunction "1_1") (pintype "passive"))
      (node (ref "U1") (pin "16") (pinfunction "PIO0_7/CTS_16") (pintype "bidirectional"))
      (node (ref "X1") (pin "5") (pinfunction "5_5") (pintype "passive"))
    )
    (net (code "51") (name "Net-(BOOT-Pad3)") (class "Default")
      (node (ref "BOOT") (pin "3") (pinfunction "3_3") (pintype "bidirectional"))
      (node (ref "BOOT") (pin "4") (pinfunction "4_4") (pintype "bidirectional"))
      (node (ref "R14") (pin "2") (pinfunction "2_2") (pintype "passive"))
    )
    (net (code "52") (name "Net-(CHG-PadA)") (class "Default")
      (node (ref "CHG") (pin "A") (pinfunction "A_A") (pintype "passive"))
      (node (ref "R15") (pin "1") (pinfunction "1_1") (pintype "passive"))
    )
    (net (code "53") (name "Net-(J1-D+)") (class "Default")
      (node (ref "J1") (pin "USB_P") (pinfunction "D+_USB_P") (pintype "bidirectional"))
      (node (ref "R3") (pin "1") (pinfunction "1_1") (pintype "passive"))
      (node (ref "U2") (pin "2") (pinfunction "IO1_2") (pintype "bidirectional"))
    )
    (net (code "54") (name "Net-(J1-D-)") (class "Default")
      (node (ref "J1") (pin "USB_M") (pinfunction "D-_USB_M") (pintype "bidirectional"))
      (node (ref "R2") (pin "1") (pinfunction "1_1") (pintype "passive"))
      (node (ref "U2") (pin "3") (pinfunction "IO2_3") (pintype "bidirectional"))
    )
    (net (code "55") (name "Net-(J8-+)") (class "Default")
      (node (ref "D1") (pin "A") (pinfunction "A_A") (pintype "passive"))
      (node (ref "J8") (pin "2") (pinfunction "+_2") (pintype "bidirectional"))
      (node (ref "U5") (pin "3") (pinfunction "VBAT_3") (pintype "power_in"))
    )
    (net (code "56") (name "Net-(L-PadA)") (class "Default")
      (node (ref "L") (pin "A") (pinfunction "A_A") (pintype "passive"))
      (node (ref "R18") (pin "2") (pinfunction "2_2") (pintype "passive"))
    )
    (net (code "57") (name "Net-(LED1-PadA)") (class "Default")
      (node (ref "LED1") (pin "A") (pinfunction "A_A") (pintype "passive"))
      (node (ref "R8") (pin "2") (pinfunction "2_2") (pintype "passive"))
    )
    (net (code "58") (name "Net-(LED2-PadA)") (class "Default")
      (node (ref "LED2") (pin "A") (pinfunction "A_A") (pintype "passive"))
      (node (ref "R9") (pin "2") (pinfunction "2_2") (pintype "passive"))
    )
    (net (code "59") (name "Net-(LED3-PadA)") (class "Default")
      (node (ref "LED3") (pin "A") (pinfunction "A_A") (pintype "passive"))
      (node (ref "R13") (pin "2") (pinfunction "2_2") (pintype "passive"))
    )
    (net (code "60") (name "Net-(Q2-PadB)") (class "Default")
      (node (ref "Q2") (pin "B") (pinfunction "B_B") (pintype "passive"))
      (node (ref "R5") (pin "1") (pinfunction "1_1") (pintype "passive"))
      (node (ref "R6") (pin "2") (pinfunction "2_2") (pintype "passive"))
      (node (ref "R7") (pin "1") (pinfunction "1_1") (pintype "passive"))
    )
    (net (code "61") (name "Net-(Q2-PadC)") (class "Default")
      (node (ref "Q2") (pin "C") (pinfunction "C_C") (pintype "passive"))
      (node (ref "R4") (pin "2") (pinfunction "2_2") (pintype "passive"))
    )
    (net (code "62") (name "Net-(Q3-PadB)") (class "Default")
      (node (ref "Q3") (pin "B") (pinfunction "B_B") (pintype "passive"))
      (node (ref "R17") (pin "1") (pinfunction "1_1") (pintype "passive"))
    )
    (net (code "63") (name "Net-(R10-Pad2)") (class "Default")
      (node (ref "R10") (pin "2") (pinfunction "2_2") (pintype "passive"))
      (node (ref "S1") (pin "3") (pinfunction "3_3") (pintype "bidirectional"))
      (node (ref "S1") (pin "4") (pinfunction "4_4") (pintype "bidirectional"))
    )
    (net (code "64") (name "Net-(R11-Pad2)") (class "Default")
      (node (ref "R11") (pin "2") (pinfunction "2_2") (pintype "passive"))
      (node (ref "S2") (pin "3") (pinfunction "3_3") (pintype "bidirectional"))
      (node (ref "S2") (pin "4") (pinfunction "4_4") (pintype "bidirectional"))
    )
    (net (code "65") (name "Net-(R16-Pad2)") (class "Default")
      (node (ref "R16") (pin "2") (pinfunction "2_2") (pintype "passive"))
      (node (ref "RESET") (pin "3") (pinfunction "3_3") (pintype "bidirectional"))
      (node (ref "RESET") (pin "4") (pinfunction "4_4") (pintype "bidirectional"))
    )
    (net (code "66") (name "Net-(SG1-2)") (class "Default")
      (node (ref "Q3") (pin "C") (pinfunction "C_C") (pintype "passive"))
      (node (ref "SG1") (pin "-") (pinfunction "2_-") (pintype "passive"))
    )
    (net (code "67") (name "Net-(U5-PROG)") (class "Default")
      (node (ref "R19") (pin "2") (pinfunction "2_2") (pintype "passive"))
      (node (ref "U5") (pin "5") (pinfunction "PROG_5") (pintype "input"))
    )
    (net (code "68") (name "Net-(U5-STAT)") (class "Default")
      (node (ref "CHG") (pin "C") (pinfunction "C_C") (pintype "passive"))
      (node (ref "U5") (pin "1") (pinfunction "STAT_1") (pintype "output"))
    )
    (net (code "69") (name "RST") (class "Default")
      (node (ref "LED3") (pin "C") (pinfunction "C_C") (pintype "passive"))
      (node (ref "R12") (pin "2") (pinfunction "2_2") (pintype "passive"))
      (node (ref "U1") (pin "2") (pinfunction "RESET/PIO0_0_2") (pintype "input"))
      (node (ref "U3") (pin "2") (pinfunction "~{RESET}_2") (pintype "passive"))
      (node (ref "X1") (pin "17") (pinfunction "17_17") (pintype "passive"))
    )
    (net (code "70") (name "RSTE") (class "Default")
      (node (ref "R11") (pin "1") (pinfunction "1_1") (pintype "passive"))
      (node (ref "U3") (pin "3") (pinfunction "~{MR}_3") (pintype "passive"))
    )
    (net (code "71") (name "USBON") (class "Default")
      (node (ref "R1") (pin "2") (pinfunction "2_2") (pintype "passive"))
      (node (ref "U1") (pin "9") (pinfunction "PIO0_3/USB_VBUS_9") (pintype "bidirectional"))
    )
    (net (code "72") (name "VBUS") (class "Default")
      (node (ref "D1") (pin "C") (pinfunction "C_C") (pintype "passive"))
      (node (ref "J1") (pin "5V") (pinfunction "VBUS_5V") (pintype "bidirectional"))
      (node (ref "J2") (pin "2") (pinfunction "2_2") (pintype "passive"))
      (node (ref "J3") (pin "2") (pinfunction "2_2") (pintype "passive"))
      (node (ref "J4") (pin "2") (pinfunction "2_2") (pintype "passive"))
      (node (ref "J5") (pin "2") (pinfunction "2_2") (pintype "passive"))
      (node (ref "J6") (pin "2") (pinfunction "2_2") (pintype "passive"))
      (node (ref "J7") (pin "2") (pinfunction "2_2") (pintype "passive"))
      (node (ref "JP3") (pin "5") (pinfunction "5_5") (pintype "passive"))
      (node (ref "L1") (pin "1") (pinfunction "1_1") (pintype "passive"))
      (node (ref "R15") (pin "2") (pinfunction "2_2") (pintype "passive"))
      (node (ref "R19") (pin "1") (pinfunction "1_1") (pintype "passive"))
      (node (ref "SG1") (pin "+") (pinfunction "1_+") (pintype "passive"))
      (node (ref "U2") (pin "4") (pinfunction "VCC_4") (pintype "bidirectional"))
      (node (ref "U5") (pin "4") (pinfunction "VIN_4") (pintype "power_in"))
      (node (ref "X1") (pin "23") (pinfunction "23_23") (pintype "passive"))
      (node (ref "X1") (pin "25") (pinfunction "25_25") (pintype "passive"))
      (node (ref "X2") (pin "7") (pinfunction "7_7") (pintype "passive"))
      (node (ref "X2") (pin "9") (pinfunction "9_9") (pintype "passive"))
    )
    (net (code "73") (name "VCC") (class "Default")
      (node (ref "C3") (pin "2") (pinfunction "2_2") (pintype "passive"))
      (node (ref "C4") (pin "2") (pinfunction "2_2") (pintype "passive"))
      (node (ref "L1") (pin "2") (pinfunction "2_2") (pintype "passive"))
      (node (ref "R1") (pin "1") (pinfunction "1_1") (pintype "passive"))
      (node (ref "U4") (pin "1") (pinfunction "VIN_1") (pintype "bidirectional"))
      (node (ref "U4") (pin "3") (pinfunction "EN_3") (pintype "bidirectional"))
    )
    (net (code "74") (name "XIN") (class "Default")
      (node (ref "C2") (pin "1") (pinfunction "1_1") (pintype "passive"))
      (node (ref "Q1") (pin "3") (pinfunction "P$2_3") (pintype "passive"))
      (node (ref "U1") (pin "4") (pinfunction "XTALIN_4") (pintype "input"))
    )
    (net (code "75") (name "XOUT") (class "Default")
      (node (ref "C1") (pin "1") (pinfunction "1_1") (pintype "passive"))
      (node (ref "Q1") (pin "1") (pinfunction "P$1_1") (pintype "passive"))
      (node (ref "U1") (pin "5") (pinfunction "XTALOUT_5") (pintype "output"))
    )
    (net (code "76") (name "unconnected-(J8-PAD1-PadNC1)") (class "Default")
      (node (ref "J8") (pin "NC1") (pinfunction "PAD1_NC1") (pintype "bidirectional"))
    )
    (net (code "77") (name "unconnected-(J8-PAD2-PadNC2)") (class "Default")
      (node (ref "J8") (pin "NC2") (pinfunction "PAD2_NC2") (pintype "bidirectional"))
    )
    (net (code "78") (name "unconnected-(JP3-Pad4)") (class "Default")
      (node (ref "JP3") (pin "4") (pinfunction "4_4") (pintype "passive"))
    )
    (net (code "79") (name "unconnected-(U4-NC{slash}ADJ-Pad4)") (class "Default")
      (node (ref "U4") (pin "4") (pinfunction "NC/ADJ_4") (pintype "bidirectional"))
    )
  )
)
